# Power_Line_12V.net
KiCad netlist of a schematic drawn in Altium Designer
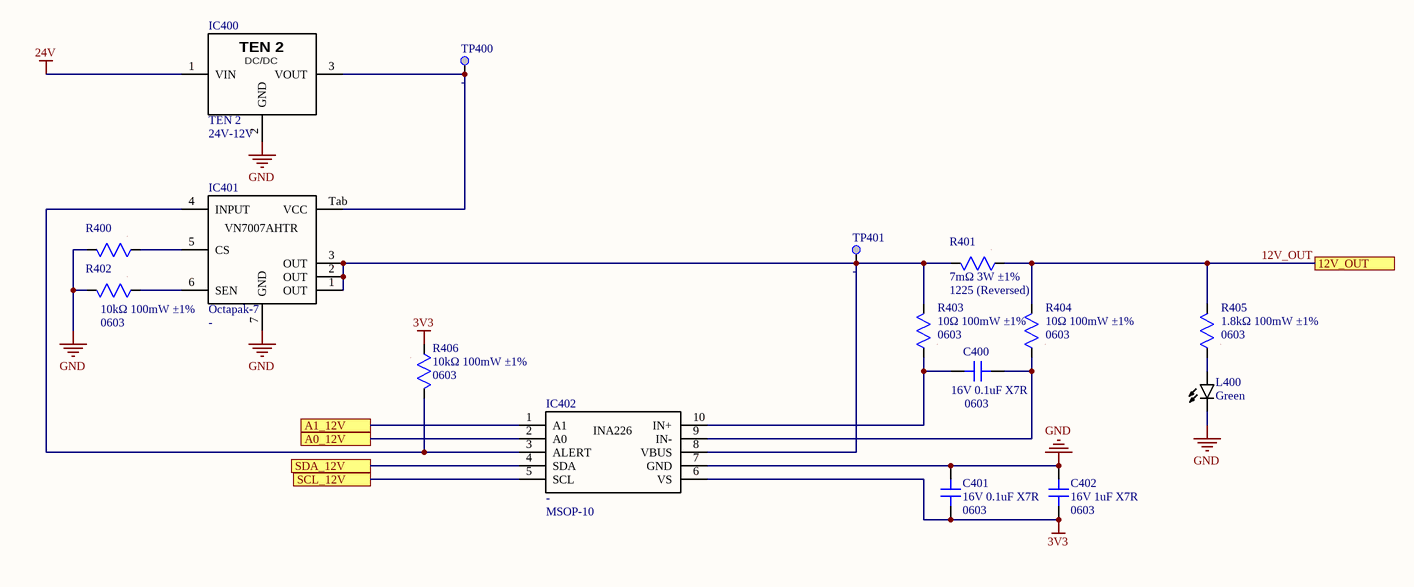
[diagram p0: Power_Line_12V.SchDoc]

(export (version "E")
  (design (tool "Eeschema 10.0.6"))
  (components
    (comp (ref "C400")
      (value "16V 0.1uF X7R")
      (footprint "CAP SMD 0603")
      (description "Condensadores de cerámica multicapa (MLCC- SMD/SMT) WCAP-CSGP 0.1uF 0603 10% 16V MLCC")
      (fields
        (field (name "PACKAGE") "0603")
        (field (name "MPN") "885012206046")
        (field (name "MANUFACTURER") "Wurth Elektronik")
      )
      (libsource (lib "eUSR_Database") (part "CAP non polarized"))
    )
    (comp (ref "C401")
      (value "16V 0.1uF X7R")
      (footprint "CAP SMD 0603")
      (description "Condensadores de cerámica multicapa (MLCC- SMD/SMT) WCAP-CSGP 0.1uF 0603 10% 16V MLCC")
      (fields
        (field (name "PACKAGE") "0603")
        (field (name "MPN") "885012206046")
        (field (name "MANUFACTURER") "Wurth Elektronik")
      )
      (libsource (lib "eUSR_Database") (part "CAP non polarized"))
    )
    (comp (ref "C402")
      (value "16V 1uF X7R")
      (footprint "CAP SMD 0603")
      (description "Condensadores de cerámica multicapa (MLCC- SMD/SMT) WCAP-CSGP 1uF 0603 10% 16V MLCC")
      (fields
        (field (name "PACKAGE") "0603")
        (field (name "MPN") "885012206052")
        (field (name "MANUFACTURER") "Wurth Elektronik")
      )
      (libsource (lib "eUSR_Database") (part "CAP non polarized"))
    )
    (comp (ref "IC400")
      (value "TEN 2")
      (footprint "TEN 2")
      (description "Convertidores DC/DC para montaje pasante 15-36Vin 12V 2A SIP switching regulator")
      (fields
        (field (name "ALTIUM_VALUE") "24V-12V")
        (field (name "MPN") "TSR 2-24120")
        (field (name "MANUFACTURER") "TRACO Power")
      )
      (libsource (lib "eUSR_Database") (part "TEN 2"))
    )
    (comp (ref "IC401")
      (value "-")
      (footprint "Octapak-7")
      (fields
        (field (name "PACKAGE") "Octapak-7")
        (field (name "MPN") "VN7007AHTR")
        (field (name "MANUFACTURER") "511-VN7007AHTR")
      )
      (libsource (lib "eUSR_Database") (part "VN7007AHTR"))
    )
    (comp (ref "IC402")
      (value "-")
      (footprint "VSOP-10")
      (fields
        (field (name "PACKAGE") "MSOP-10")
        (field (name "MPN") "INA226AIDGSR")
        (field (name "MANUFACTURER") "595-INA226AIDGSR")
        (field (name "Comment") "INA226")
      )
      (libsource (lib "eUSR_Database") (part "INA226"))
    )
    (comp (ref "L400")
      (value "Green")
      (footprint "LED SMD 0603")
      (description "LED de un solo color Green 525nm 1400mcd 2.85V 73deg 0603")
      (fields (field (name "MPN") "VLMTG1400-GS08") (field (name "MANUFACTURER") "Vishay Semiconductors"))
      (libsource (lib "eUSR_Database") (part "LED WHITE"))
    )
    (comp (ref "R400")
      (value "RES")
      (footprint "RES SMD 0603")
      (description "Resistores de película gruesa - SMD WRIS-RSKS 10 kOhms 1 % 0.1 W 0603 AEC-Q200")
      (fields (field (name "MPN") "560112116005") (field (name "MANUFACTURER") "Wurth Elektronik"))
      (libsource (lib "eUSR_Database") (part "RES"))
    )
    (comp (ref "R401")
      (value "7mΩ 3W ±1%")
      (footprint "RES SMD 1225 Reversed")
      (description "Resistores de detección de corriente - SMD 3W 0.007ohm 1% 50ppm")
      (fields
        (field (name "PACKAGE") "1225 (Reversed)")
        (field (name "MPN") "KRL6432E-M-R007-F-T1")
        (field (name "MANUFACTURER") "Susumu")
      )
      (libsource (lib "eUSR_Database") (part "RES"))
    )
    (comp (ref "R402")
      (value "10kΩ 100mW ±1%")
      (footprint "RES SMD 0603")
      (description "Resistores de película gruesa - SMD WRIS-RSKS 10 kOhms 1 % 0.1 W 0603 AEC-Q200")
      (fields
        (field (name "PACKAGE") "0603")
        (field (name "MPN") "560112116005")
        (field (name "MANUFACTURER") "Wurth Elektronik")
      )
      (libsource (lib "eUSR_Database") (part "RES"))
    )
    (comp (ref "R403")
      (value "10Ω 100mW ±1%")
      (footprint "RES SMD 0603")
      (description "Resistores de película gruesa - SMD WRIS-RSKS 10 Ohms 1 % 0.1 W 0603 AEC-Q200")
      (fields
        (field (name "PACKAGE") "0603")
        (field (name "MPN") "560112116013")
        (field (name "MANUFACTURER") "Wurth Elektronik")
      )
      (libsource (lib "eUSR_Database") (part "RES"))
    )
    (comp (ref "R404")
      (value "10Ω 100mW ±1%")
      (footprint "RES SMD 0603")
      (description "Resistores de película gruesa - SMD WRIS-RSKS 10 Ohms 1 % 0.1 W 0603 AEC-Q200")
      (fields
        (field (name "PACKAGE") "0603")
        (field (name "MPN") "560112116013")
        (field (name "MANUFACTURER") "Wurth Elektronik")
      )
      (libsource (lib "eUSR_Database") (part "RES"))
    )
    (comp (ref "R405")
      (value "1.8kΩ 100mW ±1%")
      (footprint "RES SMD 0603")
      (description "Resistores de película gruesa - SMD WRIS-RSKS 1.8 kOhms 1 % 0.1 W 0603 AEC-Q200")
      (fields
        (field (name "PACKAGE") "0603")
        (field (name "MPN") "560112116032")
        (field (name "MANUFACTURER") "Wurth Elektronik")
      )
      (libsource (lib "eUSR_Database") (part "RES"))
    )
    (comp (ref "R406")
      (value "10kΩ 100mW ±1%")
      (footprint "RES SMD 0603")
      (description "Resistores de película gruesa - SMD WRIS-RSKS 10 kOhms 1 % 0.1 W 0603 AEC-Q200")
      (fields
        (field (name "PACKAGE") "0603")
        (field (name "MPN") "560112116005")
        (field (name "MANUFACTURER") "Wurth Elektronik")
      )
      (libsource (lib "eUSR_Database") (part "RES"))
    )
    (comp (ref "TP400")
      (value "-")
      (footprint "TP_SMD_1MM")
      (description "Test Point")
      (libsource (lib "eUSR_Database") (part "TP1mm"))
    )
    (comp (ref "TP401")
      (value "-")
      (footprint "TP_SMD_1MM")
      (description "Test Point")
      (libsource (lib "eUSR_Database") (part "TP1mm"))
    )
  )
  (nets
    (net (code "1") (name "/12V_OUT") (class "Default")
      (node (ref "R401") (pin "1") (pinfunction "1_1") (pintype "passive"))
      (node (ref "R404") (pin "2") (pinfunction "2_2") (pintype "passive"))
      (node (ref "R405") (pin "2") (pinfunction "2_2") (pintype "passive"))
    )
    (net (code "2") (name "/A0_12V") (class "Default")
      (node (ref "IC402") (pin "2") (pinfunction "A0_2") (pintype "passive"))
    )
    (net (code "3") (name "/A1_12V") (class "Default")
      (node (ref "IC402") (pin "1") (pinfunction "A1_1") (pintype "passive"))
    )
    (net (code "4") (name "/SCL_12V") (class "Default")
      (node (ref "IC402") (pin "5") (pinfunction "SCL_5") (pintype "passive"))
    )
    (net (code "5") (name "/SDA_12V") (class "Default")
      (node (ref "IC402") (pin "4") (pinfunction "SDA_4") (pintype "passive"))
    )
    (net (code "6") (name "3V3") (class "Default")
      (node (ref "C401") (pin "2") (pinfunction "2_2") (pintype "passive"))
      (node (ref "C402") (pin "2") (pinfunction "2_2") (pintype "passive"))
      (node (ref "IC402") (pin "6") (pinfunction "VS_6") (pintype "passive"))
      (node (ref "R406") (pin "1") (pinfunction "1_1") (pintype "passive"))
    )
    (net (code "7") (name "24V") (class "Default")
      (node (ref "IC400") (pin "1") (pinfunction "VIN_1") (pintype "passive"))
    )
    (net (code "8") (name "GND") (class "Default")
      (node (ref "C401") (pin "1") (pinfunction "1_1") (pintype "passive"))
      (node (ref "C402") (pin "1") (pinfunction "1_1") (pintype "passive"))
      (node (ref "IC400") (pin "2") (pinfunction "GND_2") (pintype "passive"))
      (node (ref "IC401") (pin "7") (pinfunction "GND_7") (pintype "passive"))
      (node (ref "IC402") (pin "7") (pinfunction "GND_7") (pintype "passive"))
      (node (ref "L400") (pin "C") (pinfunction "C_C") (pintype "passive"))
      (node (ref "R400") (pin "2") (pinfunction "2_2") (pintype "passive"))
      (node (ref "R402") (pin "2") (pinfunction "2_2") (pintype "passive"))
    )
    (net (code "9") (name "Net-(IC400-VOUT)") (class "Default")
      (node (ref "IC400") (pin "3") (pinfunction "VOUT_3") (pintype "passive"))
      (node (ref "IC401") (pin "Tab") (pinfunction "VCC_Tab") (pintype "passive"))
      (node (ref "TP400") (pin "1") (pinfunction "1_1") (pintype "passive"))
    )
    (net (code "10") (name "Net-(IC401-CS)") (class "Default")
      (node (ref "IC401") (pin "5") (pinfunction "CS_5") (pintype "passive"))
      (node (ref "R400") (pin "1") (pinfunction "1_1") (pintype "passive"))
    )
    (net (code "11") (name "Net-(IC401-INPUT)") (class "Default")
      (node (ref "IC401") (pin "4") (pinfunction "INPUT_4") (pintype "passive"))
      (node (ref "IC402") (pin "3") (pinfunction "ALERT_3") (pintype "passive"))
      (node (ref "R406") (pin "2") (pinfunction "2_2") (pintype "passive"))
    )
    (net (code "12") (name "Net-(IC401-SEN)") (class "Default")
      (node (ref "IC401") (pin "6") (pinfunction "SEN_6") (pintype "passive"))
      (node (ref "R402") (pin "1") (pinfunction "1_1") (pintype "passive"))
    )
    (net (code "13") (name "Net-(IC402-IN+)") (class "Default")
      (node (ref "C400") (pin "1") (pinfunction "1_1") (pintype "passive"))
      (node (ref "IC402") (pin "10") (pinfunction "IN+_10") (pintype "passive"))
      (node (ref "R403") (pin "1") (pinfunction "1_1") (pintype "passive"))
    )
    (net (code "14") (name "Net-(IC402-IN-)") (class "Default")
      (node (ref "C400") (pin "2") (pinfunction "2_2") (pintype "passive"))
      (node (ref "IC402") (pin "9") (pinfunction "IN-_9") (pintype "passive"))
      (node (ref "R404") (pin "1") (pinfunction "1_1") (pintype "passive"))
    )
    (net (code "15") (name "Net-(IC402-VBUS)") (class "Default")
      (node (ref "IC401") (pin "1") (pinfunction "OUT_1") (pintype "passive"))
      (node (ref "IC401") (pin "2") (pinfunction "OUT_2") (pintype "passive"))
      (node (ref "IC401") (pin "3") (pinfunction "OUT_3") (pintype "passive"))
      (node (ref "IC402") (pin "8") (pinfunction "VBUS_8") (pintype "passive"))
      (node (ref "R401") (pin "2") (pinfunction "2_2") (pintype "passive"))
      (node (ref "R403") (pin "2") (pinfunction "2_2") (pintype "passive"))
      (node (ref "TP401") (pin "1") (pinfunction "1_1") (pintype "passive"))
    )
    (net (code "16") (name "Net-(L400-PadA)") (class "Default")
      (node (ref "L400") (pin "A") (pinfunction "A_A") (pintype "passive"))
      (node (ref "R405") (pin "1") (pinfunction "1_1") (pintype "passive"))
    )
  )
)
